# M961old.net
KiCad netlist of a schematic drawn in EAGLE
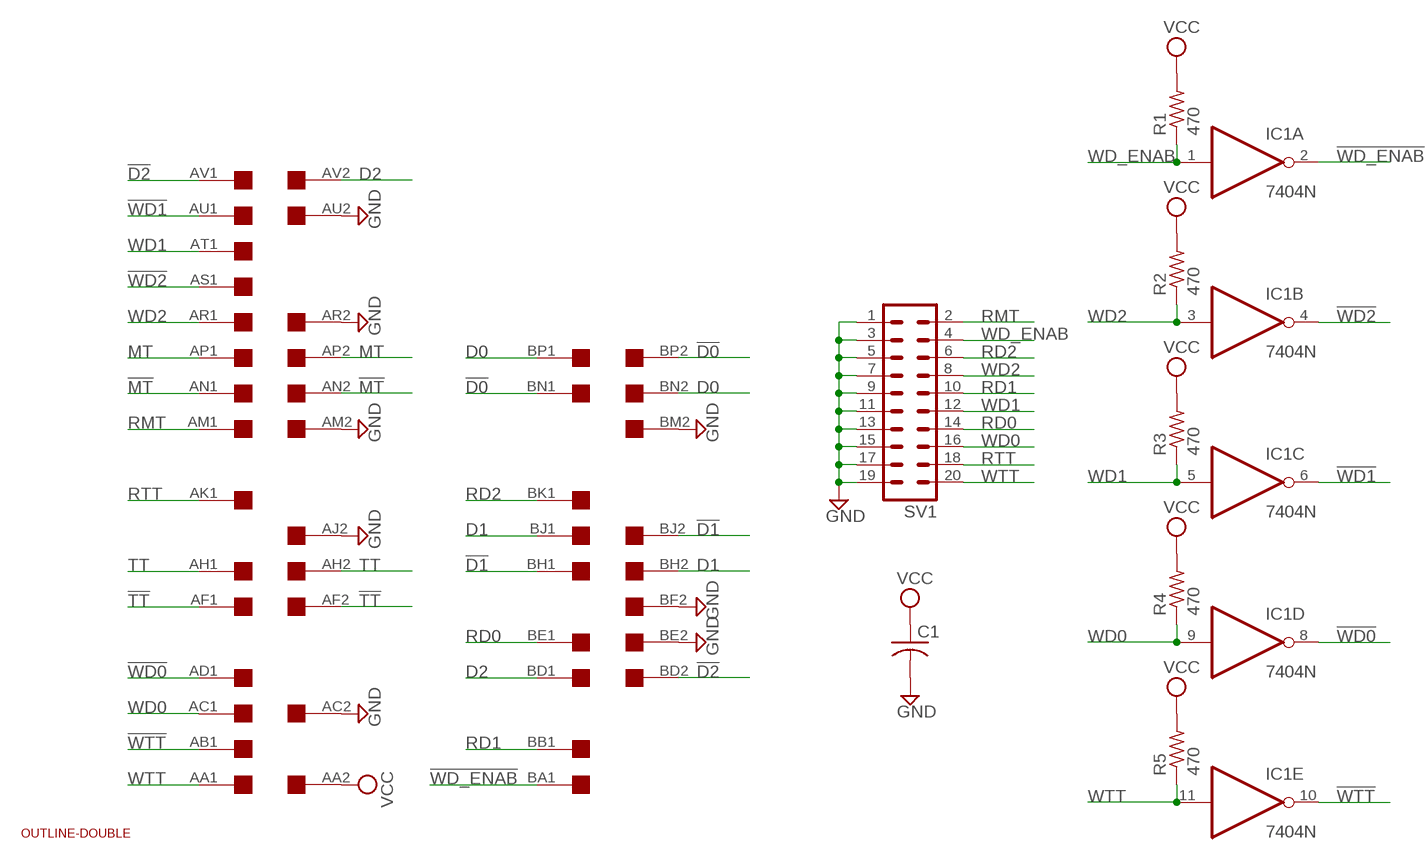
[diagram p0: schematic, sheet 1]
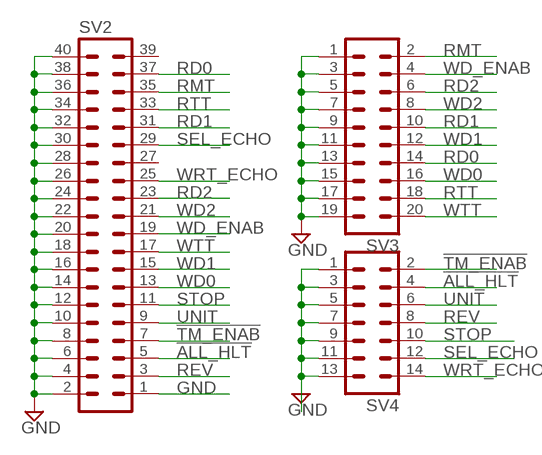
[diagram p1: schematic, sheet 2]

(export (version "E")
  (design (tool "Eeschema 10.0.6"))
  (components
    (comp (ref "SV2")
      (value "MA20-2")
      (footprint "eagle-import:MA20-2")
      (libsource (lib "eagle-import") (part "MA20-2"))
    )
    (comp (ref "SV3")
      (value "MA10-2")
      (footprint "eagle-import:MA10-2")
      (libsource (lib "eagle-import") (part "MA10-2"))
    )
    (comp (ref "SV4")
      (value "MA07-2")
      (footprint "eagle-import:MA07-2")
      (libsource (lib "eagle-import") (part "MA07-2"))
    )
    (comp (ref "C1")
      (value "C-US050-025X075")
      (footprint "eagle-import:C050-025X075")
      (libsource (lib "eagle-import") (part "C-US050-025X075"))
    )
    (comp (ref "EDGE$1")
      (value "DOUBLE")
      (footprint "eagle-import:EDGE-CON4")
      (libsource (lib "eagle-import") (part "DOUBLE"))
    )
    (comp (ref "IC1")
      (value "7404N")
      (footprint "eagle-import:DIL14")
      (libsource (lib "eagle-import") (part "7404N"))
    )
    (comp (ref "R1")
      (value "470")
      (footprint "eagle-import:0207_10")
      (libsource (lib "eagle-import") (part "R-US_0207/10"))
    )
    (comp (ref "R2")
      (value "470")
      (footprint "eagle-import:0207_10")
      (libsource (lib "eagle-import") (part "R-US_0207/10"))
    )
    (comp (ref "R3")
      (value "470")
      (footprint "eagle-import:0207_10")
      (libsource (lib "eagle-import") (part "R-US_0207/10"))
    )
    (comp (ref "R4")
      (value "470")
      (footprint "eagle-import:0207_10")
      (libsource (lib "eagle-import") (part "R-US_0207/10"))
    )
    (comp (ref "R5")
      (value "470")
      (footprint "eagle-import:0207_10")
      (libsource (lib "eagle-import") (part "R-US_0207/10"))
    )
    (comp (ref "SV1")
      (value "MA10-2")
      (footprint "eagle-import:MA10-2")
      (libsource (lib "eagle-import") (part "MA10-2"))
    )
    (comp (ref "U$2")
      (value "OUTLINE-DOUBLE")
      (footprint "eagle-import:DOUBLE")
      (libsource (lib "eagle-import") (part "OUTLINE-DOUBLE"))
    )
  )
  (nets
    (net (code "1") (name "D0") (class "Default")
      (node (ref "EDGE$1") (pin "BN2") (pinfunction "1_BN2") (pintype "bidirectional"))
      (node (ref "EDGE$1") (pin "BP1") (pinfunction "1_BP1") (pintype "bidirectional"))
    )
    (net (code "2") (name "D1") (class "Default")
      (node (ref "EDGE$1") (pin "BH2") (pinfunction "1_BH2") (pintype "bidirectional"))
      (node (ref "EDGE$1") (pin "BJ1") (pinfunction "1_BJ1") (pintype "bidirectional"))
    )
    (net (code "3") (name "D2") (class "Default")
      (node (ref "EDGE$1") (pin "AV2") (pinfunction "1_AV2") (pintype "bidirectional"))
      (node (ref "EDGE$1") (pin "BD1") (pinfunction "1_BD1") (pintype "bidirectional"))
    )
    (net (code "4") (name "GND") (class "Default")
      (node (ref "C1") (pin "2") (pinfunction "2_2") (pintype "passive"))
      (node (ref "EDGE$1") (pin "AC2") (pinfunction "1_AC2") (pintype "bidirectional"))
      (node (ref "EDGE$1") (pin "AJ2") (pinfunction "1_AJ2") (pintype "bidirectional"))
      (node (ref "EDGE$1") (pin "AM2") (pinfunction "1_AM2") (pintype "bidirectional"))
      (node (ref "EDGE$1") (pin "AR2") (pinfunction "1_AR2") (pintype "bidirectional"))
      (node (ref "EDGE$1") (pin "AU2") (pinfunction "1_AU2") (pintype "bidirectional"))
      (node (ref "EDGE$1") (pin "BE2") (pinfunction "1_BE2") (pintype "bidirectional"))
      (node (ref "EDGE$1") (pin "BF2") (pinfunction "1_BF2") (pintype "bidirectional"))
      (node (ref "EDGE$1") (pin "BM2") (pinfunction "1_BM2") (pintype "bidirectional"))
      (node (ref "SV1") (pin "1") (pinfunction "1_1") (pintype "passive"))
      (node (ref "SV1") (pin "11") (pinfunction "11_11") (pintype "passive"))
      (node (ref "SV1") (pin "13") (pinfunction "13_13") (pintype "passive"))
      (node (ref "SV1") (pin "15") (pinfunction "15_15") (pintype "passive"))
      (node (ref "SV1") (pin "17") (pinfunction "17_17") (pintype "passive"))
      (node (ref "SV1") (pin "19") (pinfunction "19_19") (pintype "passive"))
      (node (ref "SV1") (pin "3") (pinfunction "3_3") (pintype "passive"))
      (node (ref "SV1") (pin "5") (pinfunction "5_5") (pintype "passive"))
      (node (ref "SV1") (pin "7") (pinfunction "7_7") (pintype "passive"))
      (node (ref "SV1") (pin "9") (pinfunction "9_9") (pintype "passive"))
      (node (ref "SV2") (pin "1") (pinfunction "1_1") (pintype "passive"))
      (node (ref "SV2") (pin "10") (pinfunction "10_10") (pintype "passive"))
      (node (ref "SV2") (pin "12") (pinfunction "12_12") (pintype "passive"))
      (node (ref "SV2") (pin "14") (pinfunction "14_14") (pintype "passive"))
      (node (ref "SV2") (pin "16") (pinfunction "16_16") (pintype "passive"))
      (node (ref "SV2") (pin "18") (pinfunction "18_18") (pintype "passive"))
      (node (ref "SV2") (pin "2") (pinfunction "2_2") (pintype "passive"))
      (node (ref "SV2") (pin "20") (pinfunction "20_20") (pintype "passive"))
      (node (ref "SV2") (pin "22") (pinfunction "22_22") (pintype "passive"))
      (node (ref "SV2") (pin "24") (pinfunction "24_24") (pintype "passive"))
      (node (ref "SV2") (pin "26") (pinfunction "26_26") (pintype "passive"))
      (node (ref "SV2") (pin "28") (pinfunction "28_28") (pintype "passive"))
      (node (ref "SV2") (pin "30") (pinfunction "30_30") (pintype "passive"))
      (node (ref "SV2") (pin "32") (pinfunction "32_32") (pintype "passive"))
      (node (ref "SV2") (pin "34") (pinfunction "34_34") (pintype "passive"))
      (node (ref "SV2") (pin "36") (pinfunction "36_36") (pintype "passive"))
      (node (ref "SV2") (pin "38") (pinfunction "38_38") (pintype "passive"))
      (node (ref "SV2") (pin "4") (pinfunction "4_4") (pintype "passive"))
      (node (ref "SV2") (pin "40") (pinfunction "40_40") (pintype "passive"))
      (node (ref "SV2") (pin "6") (pinfunction "6_6") (pintype "passive"))
      (node (ref "SV2") (pin "8") (pinfunction "8_8") (pintype "passive"))
      (node (ref "SV3") (pin "1") (pinfunction "1_1") (pintype "passive"))
      (node (ref "SV3") (pin "11") (pinfunction "11_11") (pintype "passive"))
      (node (ref "SV3") (pin "13") (pinfunction "13_13") (pintype "passive"))
      (node (ref "SV3") (pin "15") (pinfunction "15_15") (pintype "passive"))
      (node (ref "SV3") (pin "17") (pinfunction "17_17") (pintype "passive"))
      (node (ref "SV3") (pin "19") (pinfunction "19_19") (pintype "passive"))
      (node (ref "SV3") (pin "3") (pinfunction "3_3") (pintype "passive"))
      (node (ref "SV3") (pin "5") (pinfunction "5_5") (pintype "passive"))
      (node (ref "SV3") (pin "7") (pinfunction "7_7") (pintype "passive"))
      (node (ref "SV3") (pin "9") (pinfunction "9_9") (pintype "passive"))
      (node (ref "SV4") (pin "1") (pinfunction "1_1") (pintype "passive"))
      (node (ref "SV4") (pin "11") (pinfunction "11_11") (pintype "passive"))
      (node (ref "SV4") (pin "13") (pinfunction "13_13") (pintype "passive"))
      (node (ref "SV4") (pin "3") (pinfunction "3_3") (pintype "passive"))
      (node (ref "SV4") (pin "5") (pinfunction "5_5") (pintype "passive"))
      (node (ref "SV4") (pin "7") (pinfunction "7_7") (pintype "passive"))
      (node (ref "SV4") (pin "9") (pinfunction "9_9") (pintype "passive"))
    )
    (net (code "5") (name "MT") (class "Default")
      (node (ref "EDGE$1") (pin "AP1") (pinfunction "1_AP1") (pintype "bidirectional"))
      (node (ref "EDGE$1") (pin "AP2") (pinfunction "1_AP2") (pintype "bidirectional"))
    )
    (net (code "6") (name "RD0") (class "Default")
      (node (ref "EDGE$1") (pin "BE1") (pinfunction "1_BE1") (pintype "bidirectional"))
      (node (ref "SV1") (pin "14") (pinfunction "14_14") (pintype "passive"))
      (node (ref "SV2") (pin "37") (pinfunction "37_37") (pintype "passive"))
      (node (ref "SV3") (pin "14") (pinfunction "14_14") (pintype "passive"))
    )
    (net (code "7") (name "RD1") (class "Default")
      (node (ref "EDGE$1") (pin "BB1") (pinfunction "1_BB1") (pintype "bidirectional"))
      (node (ref "SV1") (pin "10") (pinfunction "10_10") (pintype "passive"))
      (node (ref "SV2") (pin "31") (pinfunction "31_31") (pintype "passive"))
      (node (ref "SV3") (pin "10") (pinfunction "10_10") (pintype "passive"))
    )
    (net (code "8") (name "RD2") (class "Default")
      (node (ref "EDGE$1") (pin "BK1") (pinfunction "1_BK1") (pintype "bidirectional"))
      (node (ref "SV1") (pin "6") (pinfunction "6_6") (pintype "passive"))
      (node (ref "SV2") (pin "23") (pinfunction "23_23") (pintype "passive"))
      (node (ref "SV3") (pin "6") (pinfunction "6_6") (pintype "passive"))
    )
    (net (code "9") (name "REV") (class "Default")
      (node (ref "SV2") (pin "3") (pinfunction "3_3") (pintype "passive"))
      (node (ref "SV4") (pin "8") (pinfunction "8_8") (pintype "passive"))
    )
    (net (code "10") (name "RMT") (class "Default")
      (node (ref "EDGE$1") (pin "AM1") (pinfunction "1_AM1") (pintype "bidirectional"))
      (node (ref "SV1") (pin "2") (pinfunction "2_2") (pintype "passive"))
      (node (ref "SV2") (pin "35") (pinfunction "35_35") (pintype "passive"))
      (node (ref "SV3") (pin "2") (pinfunction "2_2") (pintype "passive"))
    )
    (net (code "11") (name "RTT") (class "Default")
      (node (ref "EDGE$1") (pin "AK1") (pinfunction "1_AK1") (pintype "bidirectional"))
      (node (ref "SV1") (pin "18") (pinfunction "18_18") (pintype "passive"))
      (node (ref "SV2") (pin "33") (pinfunction "33_33") (pintype "passive"))
      (node (ref "SV3") (pin "18") (pinfunction "18_18") (pintype "passive"))
    )
    (net (code "12") (name "SEL_ECHO") (class "Default")
      (node (ref "SV2") (pin "29") (pinfunction "29_29") (pintype "passive"))
      (node (ref "SV4") (pin "12") (pinfunction "12_12") (pintype "passive"))
    )
    (net (code "13") (name "STOP") (class "Default")
      (node (ref "SV2") (pin "11") (pinfunction "11_11") (pintype "passive"))
      (node (ref "SV4") (pin "10") (pinfunction "10_10") (pintype "passive"))
    )
    (net (code "14") (name "TT") (class "Default")
      (node (ref "EDGE$1") (pin "AH1") (pinfunction "1_AH1") (pintype "bidirectional"))
      (node (ref "EDGE$1") (pin "AH2") (pinfunction "1_AH2") (pintype "bidirectional"))
    )
    (net (code "15") (name "UNIT") (class "Default")
      (node (ref "SV2") (pin "9") (pinfunction "9_9") (pintype "passive"))
      (node (ref "SV4") (pin "6") (pinfunction "6_6") (pintype "passive"))
    )
    (net (code "16") (name "VCC") (class "Default")
      (node (ref "C1") (pin "1") (pinfunction "1_1") (pintype "passive"))
      (node (ref "EDGE$1") (pin "AA2") (pinfunction "1_AA2") (pintype "bidirectional"))
      (node (ref "R1") (pin "2") (pinfunction "2_2") (pintype "passive"))
      (node (ref "R2") (pin "2") (pinfunction "2_2") (pintype "passive"))
      (node (ref "R3") (pin "2") (pinfunction "2_2") (pintype "passive"))
      (node (ref "R4") (pin "2") (pinfunction "2_2") (pintype "passive"))
      (node (ref "R5") (pin "2") (pinfunction "2_2") (pintype "passive"))
    )
    (net (code "17") (name "WD0") (class "Default")
      (node (ref "EDGE$1") (pin "AC1") (pinfunction "1_AC1") (pintype "bidirectional"))
      (node (ref "IC1") (pin "9") (pinfunction "I_9") (pintype "input"))
      (node (ref "R4") (pin "1") (pinfunction "1_1") (pintype "passive"))
      (node (ref "SV1") (pin "16") (pinfunction "16_16") (pintype "passive"))
      (node (ref "SV2") (pin "13") (pinfunction "13_13") (pintype "passive"))
      (node (ref "SV3") (pin "16") (pinfunction "16_16") (pintype "passive"))
    )
    (net (code "18") (name "WD1") (class "Default")
      (node (ref "EDGE$1") (pin "AT1") (pinfunction "1_AT1") (pintype "bidirectional"))
      (node (ref "IC1") (pin "5") (pinfunction "I_5") (pintype "input"))
      (node (ref "R3") (pin "1") (pinfunction "1_1") (pintype "passive"))
      (node (ref "SV1") (pin "12") (pinfunction "12_12") (pintype "passive"))
      (node (ref "SV2") (pin "15") (pinfunction "15_15") (pintype "passive"))
      (node (ref "SV3") (pin "12") (pinfunction "12_12") (pintype "passive"))
    )
    (net (code "19") (name "WD2") (class "Default")
      (node (ref "EDGE$1") (pin "AR1") (pinfunction "1_AR1") (pintype "bidirectional"))
      (node (ref "IC1") (pin "3") (pinfunction "I_3") (pintype "input"))
      (node (ref "R2") (pin "1") (pinfunction "1_1") (pintype "passive"))
      (node (ref "SV1") (pin "8") (pinfunction "8_8") (pintype "passive"))
      (node (ref "SV2") (pin "21") (pinfunction "21_21") (pintype "passive"))
      (node (ref "SV3") (pin "8") (pinfunction "8_8") (pintype "passive"))
    )
    (net (code "20") (name "WD_ENAB") (class "Default")
      (node (ref "IC1") (pin "1") (pinfunction "I_1") (pintype "input"))
      (node (ref "R1") (pin "1") (pinfunction "1_1") (pintype "passive"))
      (node (ref "SV1") (pin "4") (pinfunction "4_4") (pintype "passive"))
      (node (ref "SV2") (pin "19") (pinfunction "19_19") (pintype "passive"))
      (node (ref "SV3") (pin "4") (pinfunction "4_4") (pintype "passive"))
    )
    (net (code "21") (name "WRT_ECHO") (class "Default")
      (node (ref "SV2") (pin "25") (pinfunction "25_25") (pintype "passive"))
      (node (ref "SV4") (pin "14") (pinfunction "14_14") (pintype "passive"))
    )
    (net (code "22") (name "WTT") (class "Default")
      (node (ref "EDGE$1") (pin "AA1") (pinfunction "1_AA1") (pintype "bidirectional"))
      (node (ref "IC1") (pin "11") (pinfunction "I_11") (pintype "input"))
      (node (ref "R5") (pin "1") (pinfunction "1_1") (pintype "passive"))
      (node (ref "SV1") (pin "20") (pinfunction "20_20") (pintype "passive"))
      (node (ref "SV2") (pin "17") (pinfunction "17_17") (pintype "passive"))
      (node (ref "SV3") (pin "20") (pinfunction "20_20") (pintype "passive"))
    )
    (net (code "23") (name "unconnected-(SV2-Pad27)") (class "Default")
      (node (ref "SV2") (pin "27") (pinfunction "27_27") (pintype "passive"))
    )
    (net (code "24") (name "unconnected-(SV2-Pad39)") (class "Default")
      (node (ref "SV2") (pin "39") (pinfunction "39_39") (pintype "passive"))
    )
    (net (code "25") (name "~{ALL_HLT}") (class "Default")
      (node (ref "SV2") (pin "5") (pinfunction "5_5") (pintype "passive"))
      (node (ref "SV4") (pin "4") (pinfunction "4_4") (pintype "passive"))
    )
    (net (code "26") (name "~{D0}") (class "Default")
      (node (ref "EDGE$1") (pin "BN1") (pinfunction "1_BN1") (pintype "bidirectional"))
      (node (ref "EDGE$1") (pin "BP2") (pinfunction "1_BP2") (pintype "bidirectional"))
    )
    (net (code "27") (name "~{D1}") (class "Default")
      (node (ref "EDGE$1") (pin "BH1") (pinfunction "1_BH1") (pintype "bidirectional"))
      (node (ref "EDGE$1") (pin "BJ2") (pinfunction "1_BJ2") (pintype "bidirectional"))
    )
    (net (code "28") (name "~{D2}") (class "Default")
      (node (ref "EDGE$1") (pin "AV1") (pinfunction "1_AV1") (pintype "bidirectional"))
      (node (ref "EDGE$1") (pin "BD2") (pinfunction "1_BD2") (pintype "bidirectional"))
    )
    (net (code "29") (name "~{MT}") (class "Default")
      (node (ref "EDGE$1") (pin "AN1") (pinfunction "1_AN1") (pintype "bidirectional"))
      (node (ref "EDGE$1") (pin "AN2") (pinfunction "1_AN2") (pintype "bidirectional"))
    )
    (net (code "30") (name "~{TM_ENAB}") (class "Default")
      (node (ref "SV2") (pin "7") (pinfunction "7_7") (pintype "passive"))
      (node (ref "SV4") (pin "2") (pinfunction "2_2") (pintype "passive"))
    )
    (net (code "31") (name "~{TT}") (class "Default")
      (node (ref "EDGE$1") (pin "AF1") (pinfunction "1_AF1") (pintype "bidirectional"))
      (node (ref "EDGE$1") (pin "AF2") (pinfunction "1_AF2") (pintype "bidirectional"))
    )
    (net (code "32") (name "~{WD0}") (class "Default")
      (node (ref "EDGE$1") (pin "AD1") (pinfunction "1_AD1") (pintype "bidirectional"))
      (node (ref "IC1") (pin "8") (pinfunction "O_8") (pintype "output"))
    )
    (net (code "33") (name "~{WD1}") (class "Default")
      (node (ref "EDGE$1") (pin "AU1") (pinfunction "1_AU1") (pintype "bidirectional"))
      (node (ref "IC1") (pin "6") (pinfunction "O_6") (pintype "output"))
    )
    (net (code "34") (name "~{WD2}") (class "Default")
      (node (ref "EDGE$1") (pin "AS1") (pinfunction "1_AS1") (pintype "bidirectional"))
      (node (ref "IC1") (pin "4") (pinfunction "O_4") (pintype "output"))
    )
    (net (code "35") (name "~{WD_ENAB}") (class "Default")
      (node (ref "EDGE$1") (pin "BA1") (pinfunction "1_BA1") (pintype "bidirectional"))
      (node (ref "IC1") (pin "2") (pinfunction "O_2") (pintype "output"))
    )
    (net (code "36") (name "~{WTT}") (class "Default")
      (node (ref "EDGE$1") (pin "AB1") (pinfunction "1_AB1") (pintype "bidirectional"))
      (node (ref "IC1") (pin "10") (pinfunction "O_10") (pintype "output"))
    )
  )
)
